# yard-ice-power.net
KiCad netlist of a schematic drawn in Altium Designer
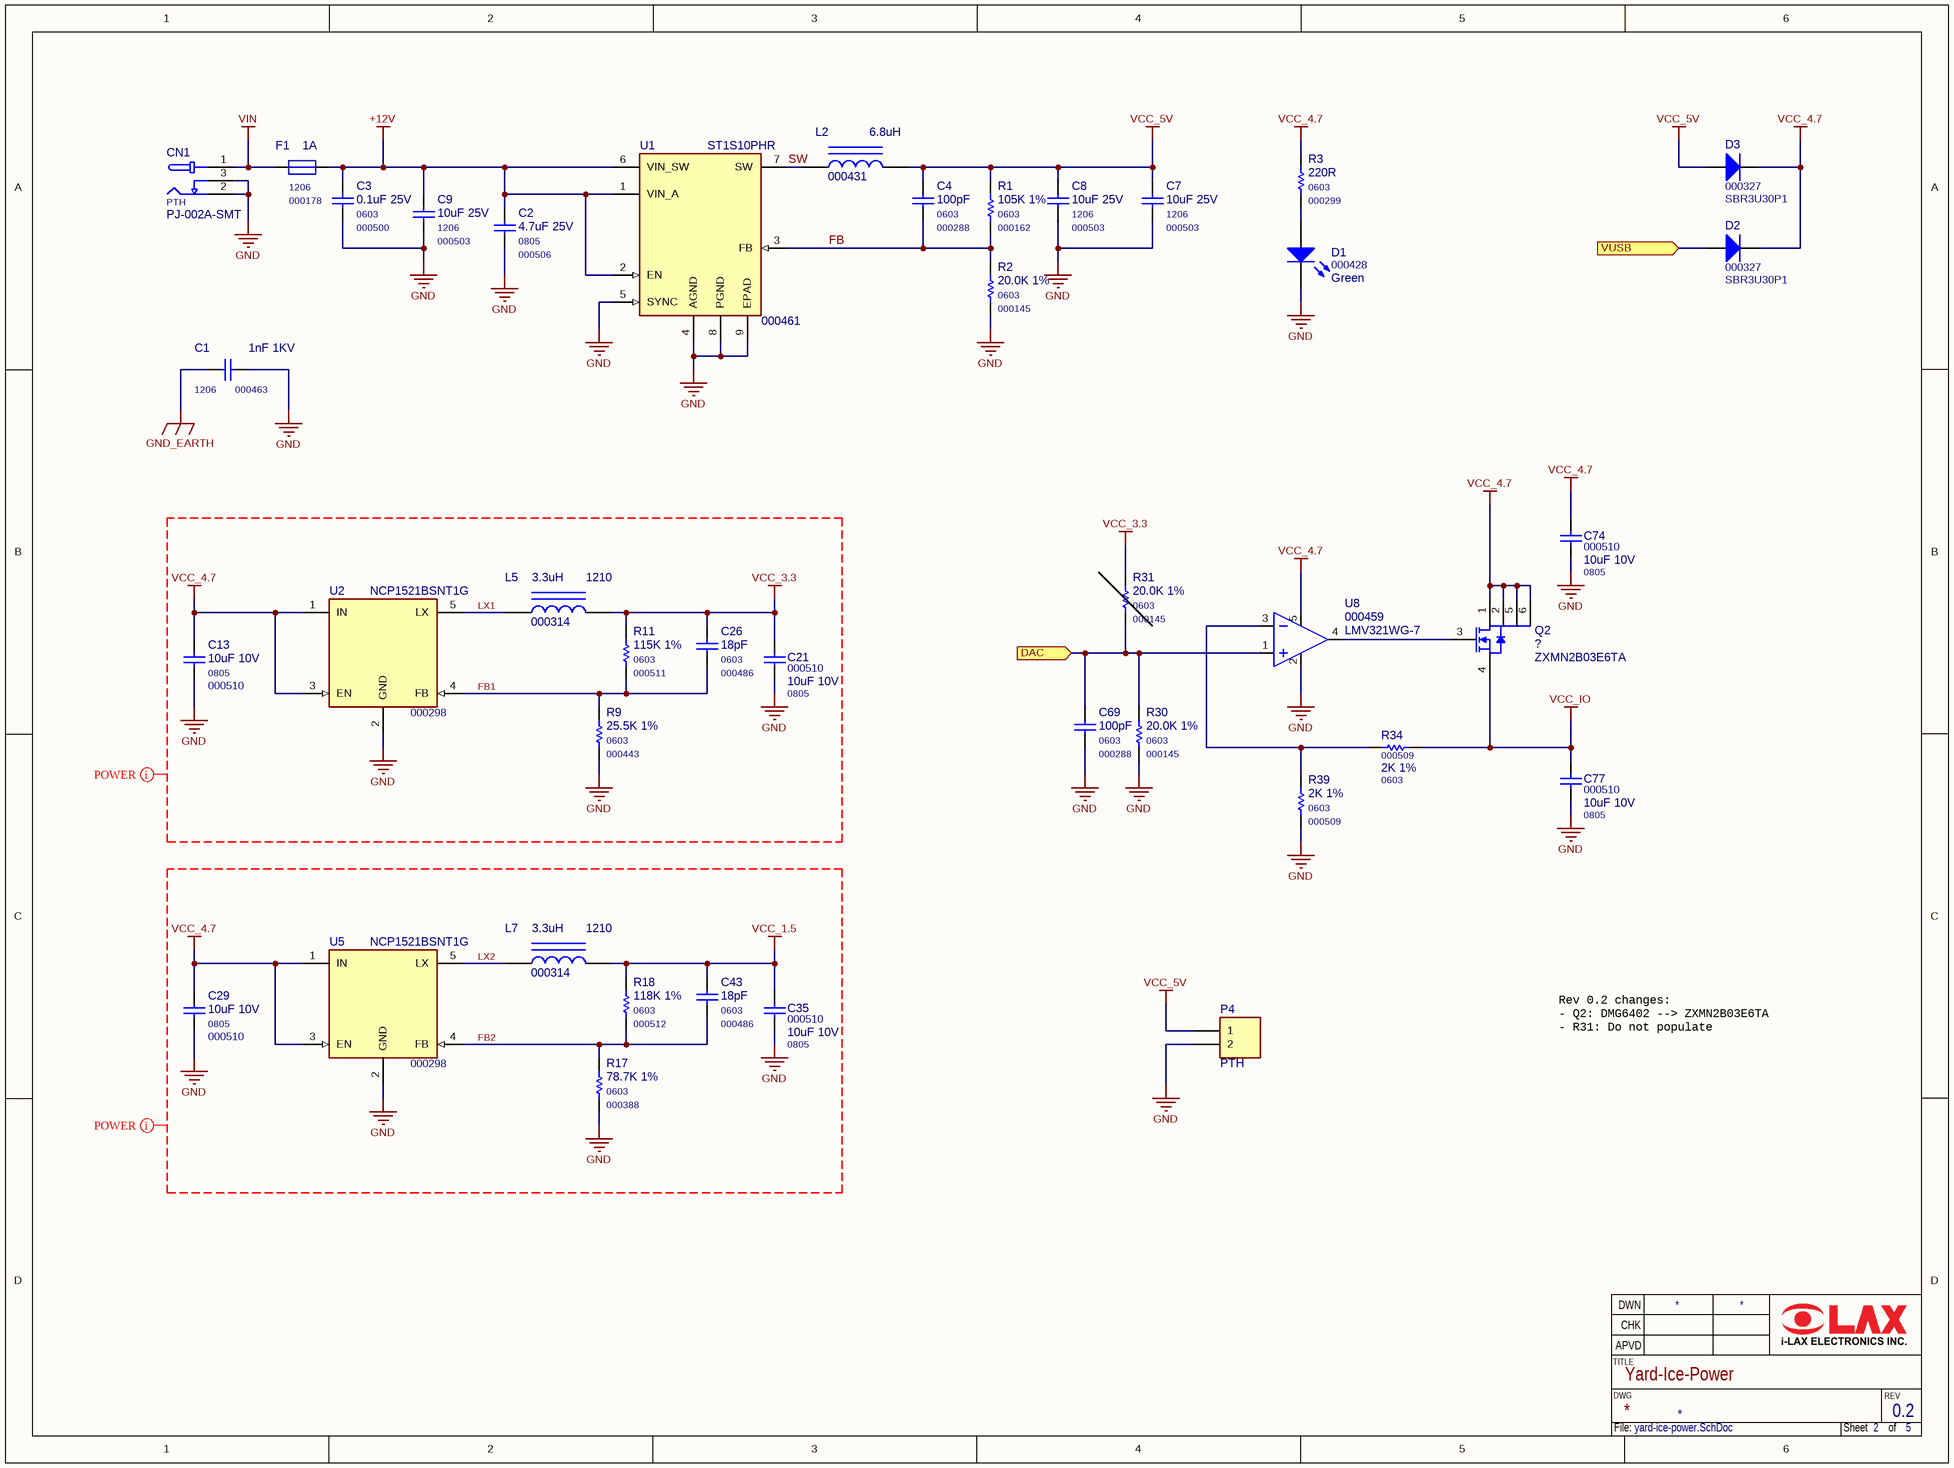
[diagram p0: yard-ice-power.SchDoc]

(export (version "E")
  (design (tool "Eeschema 10.0.6"))
  (components
    (comp (ref "C1")
      (value "000463")
      (footprint "C1206M")
      (description "SMD Ceramic Chip Capacitor - 1206")
      (fields (field (name "ALTIUM_VALUE") "1nF 1KV") (field (name "PACKAGE") "1206"))
      (libsource (lib "discrete-sm") (part "C1206"))
    )
    (comp (ref "C2")
      (value "000506")
      (footprint "C0805M")
      (description "SMD Ceramic Chip Capacitor - 0805 - X7R")
      (fields
        (field (name "ALTIUM_VALUE") "4.7uF 25V")
        (field (name "PACKAGE") "0805")
        (field (name "MF") "Taiyo Yuden")
      )
      (libsource (lib "discrete-sm") (part "C0805"))
    )
    (comp (ref "C3")
      (value "000500")
      (footprint "C0603M")
      (description "SMD Ceramic Chip Capacitor - 0603 - X7R")
      (fields
        (field (name "ALTIUM_VALUE") "0.1uF 25V")
        (field (name "PACKAGE") "0603")
        (field (name "MF") "TDK")
      )
      (libsource (lib "discrete-sm") (part "C0603"))
    )
    (comp (ref "C4")
      (value "000288")
      (footprint "C0603M")
      (description "SMD Ceramic Chip Capacitor - 0603")
      (fields (field (name "ALTIUM_VALUE") "100pF") (field (name "PACKAGE") "0603"))
      (libsource (lib "discrete-sm") (part "C0603"))
    )
    (comp (ref "C7")
      (value "000503")
      (footprint "C1206M")
      (description "SMD Ceramic Chip Capacitor - 1206 - X7R")
      (fields
        (field (name "ALTIUM_VALUE") "10uF 25V")
        (field (name "PACKAGE") "1206")
        (field (name "MF") "Taiyo Yuden")
      )
      (libsource (lib "discrete-sm") (part "C1206"))
    )
    (comp (ref "C8")
      (value "000503")
      (footprint "C1206M")
      (description "SMD Ceramic Chip Capacitor - 1206 - X7R")
      (fields
        (field (name "ALTIUM_VALUE") "10uF 25V")
        (field (name "PACKAGE") "1206")
        (field (name "MF") "Taiyo Yuden")
      )
      (libsource (lib "discrete-sm") (part "C1206"))
    )
    (comp (ref "C9")
      (value "000503")
      (footprint "C1206M")
      (description "SMD Ceramic Chip Capacitor - 1206 - X7R")
      (fields
        (field (name "ALTIUM_VALUE") "10uF 25V")
        (field (name "PACKAGE") "1206")
        (field (name "MF") "Taiyo Yuden")
      )
      (libsource (lib "discrete-sm") (part "C1206"))
    )
    (comp (ref "C13")
      (value "000510")
      (footprint "C0805M")
      (description "SMD Ceramic Chip Capacitor - 0805 - X7R")
      (fields
        (field (name "ALTIUM_VALUE") "10uF 10V")
        (field (name "PACKAGE") "0805")
        (field (name "MF") "TDK")
      )
      (libsource (lib "sm_cap") (part "C0805"))
    )
    (comp (ref "C21")
      (value "000510")
      (footprint "C0805M")
      (description "SMD Ceramic Chip Capacitor - 0805 - X7R")
      (fields
        (field (name "ALTIUM_VALUE") "10uF 10V")
        (field (name "PACKAGE") "0805")
        (field (name "MF") "TDK")
      )
      (libsource (lib "sm_cap") (part "C0805"))
    )
    (comp (ref "C26")
      (value "000486")
      (footprint "C0603M")
      (description "SMD Ceramic Chip Capacitor - 0603")
      (fields (field (name "ALTIUM_VALUE") "18pF") (field (name "PACKAGE") "0603"))
      (libsource (lib "discrete-sm") (part "C0603"))
    )
    (comp (ref "C29")
      (value "000510")
      (footprint "C0805M")
      (description "SMD Ceramic Chip Capacitor - 0805 - X7R")
      (fields
        (field (name "ALTIUM_VALUE") "10uF 10V")
        (field (name "PACKAGE") "0805")
        (field (name "MF") "TDK")
      )
      (libsource (lib "sm_cap") (part "C0805"))
    )
    (comp (ref "C35")
      (value "000510")
      (footprint "C0805M")
      (description "SMD Ceramic Chip Capacitor - 0805 - X7R")
      (fields
        (field (name "ALTIUM_VALUE") "10uF 10V")
        (field (name "PACKAGE") "0805")
        (field (name "MF") "TDK")
      )
      (libsource (lib "sm_cap") (part "C0805"))
    )
    (comp (ref "C43")
      (value "000486")
      (footprint "C0603M")
      (description "SMD Ceramic Chip Capacitor - 0603")
      (fields (field (name "ALTIUM_VALUE") "18pF") (field (name "PACKAGE") "0603"))
      (libsource (lib "discrete-sm") (part "C0603"))
    )
    (comp (ref "C69")
      (value "000288")
      (footprint "C0603M")
      (description "SMD Ceramic Chip Capacitor - 0603")
      (fields (field (name "ALTIUM_VALUE") "100pF") (field (name "PACKAGE") "0603"))
      (libsource (lib "discrete-sm") (part "C0603"))
    )
    (comp (ref "C74")
      (value "TDK")
      (footprint "C0805M")
      (description "SMD Ceramic Chip Capacitor - 0805 - X7R")
      (fields (field (name "ALTIUM_VALUE") "10uF 10V") (field (name "PACKAGE") "0805"))
      (libsource (lib "sm_cap") (part "C0805"))
    )
    (comp (ref "C77")
      (value "TDK")
      (footprint "C0805M")
      (description "SMD Ceramic Chip Capacitor - 0805 - X7R")
      (fields (field (name "ALTIUM_VALUE") "10uF 10V") (field (name "PACKAGE") "0805"))
      (libsource (lib "sm_cap") (part "C0805"))
    )
    (comp (ref "CN1")
      (value "PTH")
      (footprint "PJ-002A-SMT")
      (description "Low Voltage Power Supply Connector")
      (fields (field (name "MF") "CUI INC") (field (name "MF PN") "PJ-002A-SMT"))
      (libsource (lib "cui") (part "PJ-002A-SMT"))
    )
    (comp (ref "D1")
      (value "000428")
      (footprint "LED0805L LP")
      (description "LED SMD 0805")
      (fields (field (name "ALTIUM_VALUE") "Green"))
      (libsource (lib "discrete-sm") (part "LED0805LP"))
    )
    (comp (ref "D2")
      (value "000327")
      (footprint "PowerDI 123")
      (description "Super Barrier Rectifier")
      (fields (field (name "ALTIUM_VALUE") "SBR3U30P1") (field (name "MF") "Diodes Inc"))
      (libsource (lib "diodes-inc") (part "SBR3U30P1"))
    )
    (comp (ref "D3")
      (value "000327")
      (footprint "PowerDI 123")
      (description "Super Barrier Rectifier")
      (fields (field (name "ALTIUM_VALUE") "SBR3U30P1") (field (name "MF") "Diodes Inc"))
      (libsource (lib "diodes-inc") (part "SBR3U30P1"))
    )
    (comp (ref "F1")
      (value "000178")
      (footprint "F1206L")
      (description "SMD Fuse, 1A, Slow, 63VDC, 1206")
      (fields
        (field (name "ALTIUM_VALUE") "1A")
        (field (name "PACKAGE") "1206")
        (field (name "MF") "Bel Fuse Inc")
      )
      (libsource (lib "discrete-sm") (part "F1206"))
    )
    (comp (ref "L2")
      (value "000431")
      (footprint "L8.0MMX8.0MM")
      (description "SMT Power Inductor 8.0X8.0mm")
      (fields (field (name "ALTIUM_VALUE") "6.8uH") (field (name "MF") "Taiyo Yuden"))
      (libsource (lib "discrete-sm") (part "L8.0X8.0"))
    )
    (comp (ref "L5")
      (value "000314")
      (footprint "L1210M")
      (description "SMD Wire Wound Inductor -  1210 (3225 metric)")
      (fields
        (field (name "MF") "Murata")
        (field (name "PACKAGE") "1210")
        (field (name "ALTIUM_VALUE") "3.3uH")
      )
      (libsource (lib "discrete-sm") (part "L1210"))
    )
    (comp (ref "L7")
      (value "000314")
      (footprint "L1210M")
      (description "SMD Wire Wound Inductor -  1210 (3225 metric)")
      (fields
        (field (name "MF") "Murata")
        (field (name "PACKAGE") "1210")
        (field (name "ALTIUM_VALUE") "3.3uH")
      )
      (libsource (lib "discrete-sm") (part "L1210"))
    )
    (comp (ref "P4")
      (value "PTH")
      (footprint "TSW-102-07-G-S")
      (description "Header, 2-Pin")
      (libsource (lib "samtec-board-to-board") (part "Header 2"))
    )
    (comp (ref "Q2")
      (value "?")
      (footprint "SOT-26")
      (description "N-Channel MOSFET, 30V, 5.3A")
      (fields (field (name "ALTIUM_VALUE") "ZXMN2B03E6TA") (field (name "MF") "Diodes Inc."))
      (libsource (lib "diodes-inc") (part "ZXMN10A08E6"))
    )
    (comp (ref "R1")
      (value "000162")
      (footprint "R0603M")
      (description "SMD Chip Resistor - 0603")
      (fields (field (name "ALTIUM_VALUE") "105K 1%") (field (name "PACKAGE") "0603"))
      (libsource (lib "discrete-sm") (part "R0603"))
    )
    (comp (ref "R2")
      (value "000145")
      (footprint "R0603M")
      (description "SMD Chip Resistor - 0603")
      (fields (field (name "ALTIUM_VALUE") "20.0K 1%") (field (name "PACKAGE") "0603"))
      (libsource (lib "discrete-sm") (part "R0603"))
    )
    (comp (ref "R3")
      (value "000299")
      (footprint "R0603M")
      (description "SMD Chip Resistor - 0603")
      (fields (field (name "ALTIUM_VALUE") "220R") (field (name "PACKAGE") "0603"))
      (libsource (lib "discrete-sm") (part "R0603"))
    )
    (comp (ref "R9")
      (value "000443")
      (footprint "R0603M")
      (description "SMD Chip Resistor - 0603")
      (fields (field (name "ALTIUM_VALUE") "25.5K 1%") (field (name "PACKAGE") "0603"))
      (libsource (lib "discrete-sm") (part "R0603"))
    )
    (comp (ref "R11")
      (value "000511")
      (footprint "R0603M")
      (description "SMD Chip Resistor - 0603")
      (fields (field (name "ALTIUM_VALUE") "115K 1%") (field (name "PACKAGE") "0603"))
      (libsource (lib "discrete-sm") (part "R0603"))
    )
    (comp (ref "R17")
      (value "000388")
      (footprint "R0603M")
      (description "SMD Chip Resistor - 0603")
      (fields (field (name "ALTIUM_VALUE") "78.7K 1%") (field (name "PACKAGE") "0603"))
      (libsource (lib "discrete-sm") (part "R0603"))
    )
    (comp (ref "R18")
      (value "000512")
      (footprint "R0603M")
      (description "SMD Chip Resistor - 0603")
      (fields (field (name "ALTIUM_VALUE") "118K 1%") (field (name "PACKAGE") "0603"))
      (libsource (lib "discrete-sm") (part "R0603"))
    )
    (comp (ref "R30")
      (value "000145")
      (footprint "R0603M")
      (description "SMD Chip Resistor - 0603")
      (fields (field (name "ALTIUM_VALUE") "20.0K 1%") (field (name "PACKAGE") "0603"))
      (libsource (lib "discrete-sm") (part "R0603"))
    )
    (comp (ref "R31")
      (value "000145")
      (footprint "R0603M")
      (description "SMD Chip Resistor - 0603")
      (fields (field (name "ALTIUM_VALUE") "20.0K 1%") (field (name "PACKAGE") "0603"))
      (libsource (lib "discrete-sm") (part "R0603"))
    )
    (comp (ref "R34")
      (value "000509")
      (footprint "R0603M")
      (description "SMD Chip Resistor - 0603")
      (fields (field (name "ALTIUM_VALUE") "2K 1%") (field (name "PACKAGE") "0603"))
      (libsource (lib "discrete-sm") (part "R0603"))
    )
    (comp (ref "R39")
      (value "000509")
      (footprint "R0603M")
      (description "SMD Chip Resistor - 0603")
      (fields (field (name "ALTIUM_VALUE") "2K 1%") (field (name "PACKAGE") "0603"))
      (libsource (lib "discrete-sm") (part "R0603"))
    )
    (comp (ref "U1")
      (value "000461")
      (footprint "PowerSO-8")
      (description "3A, 900kHZ, monolithic synchronous step-down regulator")
      (fields (field (name "ALTIUM_VALUE") "ST1S10PHR") (field (name "MF") "ST"))
      (libsource (lib "st-pwr-mgmt") (part "ST1S10"))
    )
    (comp (ref "U2")
      (value "000298")
      (footprint "TSOP-5")
      (description "1.5 MHz, 600 mA Step-Down  DC-DC Converter")
      (fields (field (name "MF") "ON Semiconductor") (field (name "ALTIUM_VALUE") "NCP1521BSNT1G"))
      (libsource (lib "on-semi") (part "NCP1521BSNT1G"))
    )
    (comp (ref "U5")
      (value "000298")
      (footprint "TSOP-5")
      (description "1.5 MHz, 600 mA Step-Down  DC-DC Converter")
      (fields (field (name "MF") "ON Semiconductor") (field (name "ALTIUM_VALUE") "NCP1521BSNT1G"))
      (libsource (lib "on-semi") (part "NCP1521BSNT1G"))
    )
    (comp (ref "U8")
      (value "000459")
      (footprint "SOT-25")
      (description "General Purpose, Low Voltage, Rail-to-Rail Output Operational Amplifier")
      (fields (field (name "ALTIUM_VALUE") "LMV321WG-7") (field (name "MF") "Diodes Inc"))
      (libsource (lib "diodes-inc-opamp") (part "LMV321WG-7"))
    )
  )
  (nets
    (net (code "1") (name "+12V") (class "Default")
      (node (ref "C2") (pin "1") (pinfunction "1_1") (pintype "passive"))
      (node (ref "C3") (pin "1") (pinfunction "1_1") (pintype "passive"))
      (node (ref "C9") (pin "1") (pinfunction "1_1") (pintype "passive"))
      (node (ref "F1") (pin "2") (pinfunction "2_2") (pintype "passive"))
      (node (ref "U1") (pin "1") (pinfunction "VIN_A_1") (pintype "power_in"))
      (node (ref "U1") (pin "2") (pinfunction "EN_2") (pintype "input"))
      (node (ref "U1") (pin "6") (pinfunction "VIN_SW_6") (pintype "power_in"))
    )
    (net (code "2") (name "/DAC") (class "Default")
      (node (ref "C69") (pin "1") (pinfunction "1_1") (pintype "passive"))
      (node (ref "R30") (pin "2") (pinfunction "2_2") (pintype "passive"))
      (node (ref "R31") (pin "1") (pinfunction "1_1") (pintype "passive"))
      (node (ref "U8") (pin "1") (pinfunction "IN+_1") (pintype "passive"))
    )
    (net (code "3") (name "/FB") (class "Default")
      (node (ref "C4") (pin "2") (pinfunction "2_2") (pintype "passive"))
      (node (ref "R1") (pin "1") (pinfunction "1_1") (pintype "passive"))
      (node (ref "R2") (pin "2") (pinfunction "2_2") (pintype "passive"))
      (node (ref "U1") (pin "3") (pinfunction "FB_3") (pintype "input"))
    )
    (net (code "4") (name "/FB1") (class "Default")
      (node (ref "C26") (pin "2") (pinfunction "2_2") (pintype "passive"))
      (node (ref "R11") (pin "1") (pinfunction "1_1") (pintype "passive"))
      (node (ref "R9") (pin "2") (pinfunction "2_2") (pintype "passive"))
      (node (ref "U2") (pin "4") (pinfunction "FB_4") (pintype "input"))
    )
    (net (code "5") (name "/FB2") (class "Default")
      (node (ref "C43") (pin "2") (pinfunction "2_2") (pintype "passive"))
      (node (ref "R17") (pin "2") (pinfunction "2_2") (pintype "passive"))
      (node (ref "R18") (pin "1") (pinfunction "1_1") (pintype "passive"))
      (node (ref "U5") (pin "4") (pinfunction "FB_4") (pintype "input"))
    )
    (net (code "6") (name "/LX1") (class "Default")
      (node (ref "L5") (pin "1") (pinfunction "1_1") (pintype "passive"))
      (node (ref "U2") (pin "5") (pinfunction "LX_5") (pintype "open_collector"))
    )
    (net (code "7") (name "/LX2") (class "Default")
      (node (ref "L7") (pin "1") (pinfunction "1_1") (pintype "passive"))
      (node (ref "U5") (pin "5") (pinfunction "LX_5") (pintype "open_collector"))
    )
    (net (code "8") (name "/SW") (class "Default")
      (node (ref "L2") (pin "1") (pinfunction "1_1") (pintype "passive"))
      (node (ref "U1") (pin "7") (pinfunction "SW_7") (pintype "open_collector"))
    )
    (net (code "9") (name "/VUSB") (class "Default")
      (node (ref "D2") (pin "1") (pinfunction "A_1") (pintype "passive"))
    )
    (net (code "10") (name "GND") (class "Default")
      (node (ref "C1") (pin "2") (pinfunction "2_2") (pintype "passive"))
      (node (ref "C13") (pin "2") (pinfunction "2_2") (pintype "passive"))
      (node (ref "C2") (pin "2") (pinfunction "2_2") (pintype "passive"))
      (node (ref "C21") (pin "2") (pinfunction "2_2") (pintype "passive"))
      (node (ref "C29") (pin "2") (pinfunction "2_2") (pintype "passive"))
      (node (ref "C3") (pin "2") (pinfunction "2_2") (pintype "passive"))
      (node (ref "C35") (pin "2") (pinfunction "2_2") (pintype "passive"))
      (node (ref "C69") (pin "2") (pinfunction "2_2") (pintype "passive"))
      (node (ref "C7") (pin "2") (pinfunction "2_2") (pintype "passive"))
      (node (ref "C74") (pin "2") (pinfunction "2_2") (pintype "passive"))
      (node (ref "C77") (pin "2") (pinfunction "2_2") (pintype "passive"))
      (node (ref "C8") (pin "2") (pinfunction "2_2") (pintype "passive"))
      (node (ref "C9") (pin "2") (pinfunction "2_2") (pintype "passive"))
      (node (ref "CN1") (pin "2") (pinfunction "2_2") (pintype "power_in"))
      (node (ref "CN1") (pin "3") (pinfunction "3_3") (pintype "power_in"))
      (node (ref "D1") (pin "2") (pinfunction "K_2") (pintype "passive"))
      (node (ref "P4") (pin "2") (pinfunction "2_2") (pintype "passive"))
      (node (ref "R17") (pin "1") (pinfunction "1_1") (pintype "passive"))
      (node (ref "R2") (pin "1") (pinfunction "1_1") (pintype "passive"))
      (node (ref "R30") (pin "1") (pinfunction "1_1") (pintype "passive"))
      (node (ref "R39") (pin "1") (pinfunction "1_1") (pintype "passive"))
      (node (ref "R9") (pin "1") (pinfunction "1_1") (pintype "passive"))
      (node (ref "U1") (pin "4") (pinfunction "AGND_4") (pintype "power_in"))
      (node (ref "U1") (pin "5") (pinfunction "SYNC_5") (pintype "input"))
      (node (ref "U1") (pin "8") (pinfunction "PGND_8") (pintype "power_in"))
      (node (ref "U1") (pin "9") (pinfunction "EPAD_9") (pintype "power_in"))
      (node (ref "U2") (pin "2") (pinfunction "GND_2") (pintype "power_in"))
      (node (ref "U5") (pin "2") (pinfunction "GND_2") (pintype "power_in"))
      (node (ref "U8") (pin "2") (pinfunction "V-_2") (pintype "power_in"))
    )
    (net (code "11") (name "GND_EARTH") (class "Default")
      (node (ref "C1") (pin "1") (pinfunction "1_1") (pintype "passive"))
    )
    (net (code "12") (name "Net-(D1-A)") (class "Default")
      (node (ref "D1") (pin "1") (pinfunction "A_1") (pintype "passive"))
      (node (ref "R3") (pin "1") (pinfunction "1_1") (pintype "passive"))
    )
    (net (code "13") (name "Net-(Q2-G)") (class "Default")
      (node (ref "Q2") (pin "3") (pinfunction "G_3") (pintype "passive"))
      (node (ref "U8") (pin "4") (pinfunction "OUT_4") (pintype "passive"))
    )
    (net (code "14") (name "Net-(U8-IN-)") (class "Default")
      (node (ref "R34") (pin "2") (pinfunction "2_2") (pintype "passive"))
      (node (ref "R39") (pin "2") (pinfunction "2_2") (pintype "passive"))
      (node (ref "U8") (pin "3") (pinfunction "IN-_3") (pintype "passive"))
    )
    (net (code "15") (name "VCC_1.5") (class "Default")
      (node (ref "C35") (pin "1") (pinfunction "1_1") (pintype "passive"))
      (node (ref "C43") (pin "1") (pinfunction "1_1") (pintype "passive"))
      (node (ref "L7") (pin "2") (pinfunction "2_2") (pintype "passive"))
      (node (ref "R18") (pin "2") (pinfunction "2_2") (pintype "passive"))
    )
    (net (code "16") (name "VCC_3.3") (class "Default")
      (node (ref "C21") (pin "1") (pinfunction "1_1") (pintype "passive"))
      (node (ref "C26") (pin "1") (pinfunction "1_1") (pintype "passive"))
      (node (ref "L5") (pin "2") (pinfunction "2_2") (pintype "passive"))
      (node (ref "R11") (pin "2") (pinfunction "2_2") (pintype "passive"))
      (node (ref "R31") (pin "2") (pinfunction "2_2") (pintype "passive"))
    )
    (net (code "17") (name "VCC_4.7") (class "Default")
      (node (ref "C13") (pin "1") (pinfunction "1_1") (pintype "passive"))
      (node (ref "C29") (pin "1") (pinfunction "1_1") (pintype "passive"))
      (node (ref "C74") (pin "1") (pinfunction "1_1") (pintype "passive"))
      (node (ref "D2") (pin "2") (pinfunction "K_2") (pintype "passive"))
      (node (ref "D3") (pin "2") (pinfunction "K_2") (pintype "passive"))
      (node (ref "Q2") (pin "1") (pinfunction "D_1") (pintype "passive"))
      (node (ref "Q2") (pin "2") (pinfunction "D_2") (pintype "passive"))
      (node (ref "Q2") (pin "5") (pinfunction "D_5") (pintype "passive"))
      (node (ref "Q2") (pin "6") (pinfunction "D_6") (pintype "passive"))
      (node (ref "R3") (pin "2") (pinfunction "2_2") (pintype "passive"))
      (node (ref "U2") (pin "1") (pinfunction "IN_1") (pintype "power_in"))
      (node (ref "U2") (pin "3") (pinfunction "EN_3") (pintype "input"))
      (node (ref "U5") (pin "1") (pinfunction "IN_1") (pintype "power_in"))
      (node (ref "U5") (pin "3") (pinfunction "EN_3") (pintype "input"))
      (node (ref "U8") (pin "5") (pinfunction "V+_5") (pintype "power_in"))
    )
    (net (code "18") (name "VCC_5V") (class "Default")
      (node (ref "C4") (pin "1") (pinfunction "1_1") (pintype "passive"))
      (node (ref "C7") (pin "1") (pinfunction "1_1") (pintype "passive"))
      (node (ref "C8") (pin "1") (pinfunction "1_1") (pintype "passive"))
      (node (ref "D3") (pin "1") (pinfunction "A_1") (pintype "passive"))
      (node (ref "L2") (pin "2") (pinfunction "2_2") (pintype "passive"))
      (node (ref "P4") (pin "1") (pinfunction "1_1") (pintype "passive"))
      (node (ref "R1") (pin "2") (pinfunction "2_2") (pintype "passive"))
    )
    (net (code "19") (name "VCC_IO") (class "Default")
      (node (ref "C77") (pin "1") (pinfunction "1_1") (pintype "passive"))
      (node (ref "Q2") (pin "4") (pinfunction "S_4") (pintype "passive"))
      (node (ref "R34") (pin "1") (pinfunction "1_1") (pintype "passive"))
    )
    (net (code "20") (name "VIN") (class "Default")
      (node (ref "CN1") (pin "1") (pinfunction "1_1") (pintype "power_in"))
      (node (ref "F1") (pin "1") (pinfunction "1_1") (pintype "passive"))
    )
  )
)
